# jsduino.net
KiCad netlist of a schematic drawn in Altium Designer
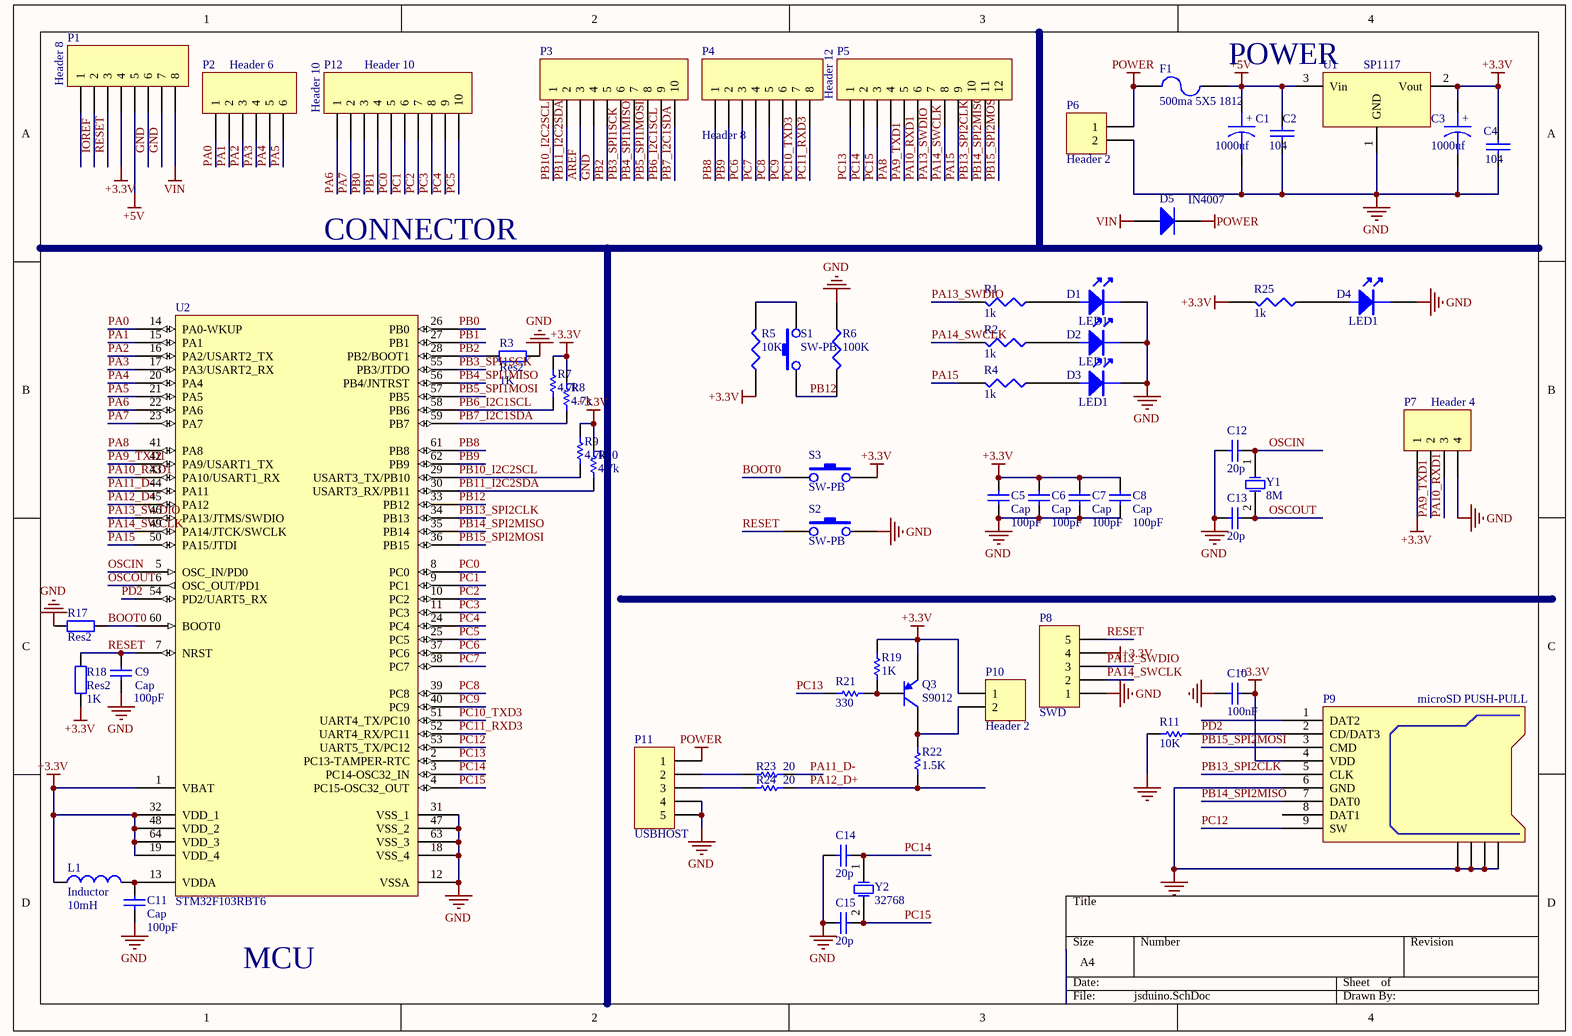
[diagram p0: jsduino.SchDoc]

(export (version "E")
  (design (tool "Eeschema 10.0.6"))
  (components
    (comp (ref "C1")
      (value "1000uf")
      (footprint "c6.3*5.3")
      (description "Capacitor")
      (libsource (lib "*") (part "CAPACITOR POL"))
    )
    (comp (ref "C2")
      (value "104")
      (footprint "0603CC")
      (description "Capacitor")
      (libsource (lib "*") (part "CAP"))
    )
    (comp (ref "C3")
      (value "104")
      (footprint "0603CC")
      (description "Capacitor")
      (libsource (lib "*") (part "CAP"))
    )
    (comp (ref "C4")
      (value "1000uf")
      (footprint "c6.3*5.3")
      (description "Capacitor")
      (libsource (lib "*") (part "CAPACITOR POL"))
    )
    (comp (ref "C5")
      (value "Cap")
      (footprint "0603CC")
      (description "Capacitor")
      (fields (field (name "ALTIUM_VALUE") "100pF") (field (name "PUBLISHER") "Altium Limited"))
      (libsource (lib "Miscellaneous Devices") (part "Cap"))
    )
    (comp (ref "C6")
      (value "Cap")
      (footprint "0603CC")
      (description "Capacitor")
      (fields (field (name "ALTIUM_VALUE") "100pF") (field (name "PUBLISHER") "Altium Limited"))
      (libsource (lib "Miscellaneous Devices") (part "Cap"))
    )
    (comp (ref "C7")
      (value "Cap")
      (footprint "0603CC")
      (description "Capacitor")
      (fields (field (name "ALTIUM_VALUE") "100pF") (field (name "PUBLISHER") "Altium Limited"))
      (libsource (lib "Miscellaneous Devices") (part "Cap"))
    )
    (comp (ref "C8")
      (value "Cap")
      (footprint "0603CC")
      (description "Capacitor")
      (fields (field (name "ALTIUM_VALUE") "100pF") (field (name "PUBLISHER") "Altium Limited"))
      (libsource (lib "Miscellaneous Devices") (part "Cap"))
    )
    (comp (ref "C9")
      (value "Cap")
      (footprint "0603CC")
      (description "Capacitor")
      (fields (field (name "ALTIUM_VALUE") "100pF") (field (name "PUBLISHER") "Altium Limited"))
      (libsource (lib "Miscellaneous Devices") (part "Cap"))
    )
    (comp (ref "C10") (value "100nF") (footprint "0603CC") (libsource (lib "") (part "CAP_1")))
    (comp (ref "C11")
      (value "Cap")
      (footprint "0603CC")
      (description "Capacitor")
      (fields (field (name "ALTIUM_VALUE") "100pF") (field (name "PUBLISHER") "Altium Limited"))
      (libsource (lib "Miscellaneous Devices") (part "Cap"))
    )
    (comp (ref "C12")
      (value "20p")
      (footprint "0603CC")
      (description "Capacitor")
      (fields (field (name "Comment") "Cap") (field (name "PUBLISHER") "Altium Limited"))
      (libsource (lib "Miscellaneous Devices") (part "Cap"))
    )
    (comp (ref "C13")
      (value "20p")
      (footprint "0603CC")
      (description "Capacitor")
      (fields (field (name "Comment") "Cap") (field (name "PUBLISHER") "Altium Limited"))
      (libsource (lib "Miscellaneous Devices") (part "Cap"))
    )
    (comp (ref "C14")
      (value "20p")
      (footprint "0603CC")
      (description "Capacitor")
      (fields (field (name "Comment") "Cap") (field (name "PUBLISHER") "Altium Limited"))
      (libsource (lib "Miscellaneous Devices") (part "Cap"))
    )
    (comp (ref "C15")
      (value "20p")
      (footprint "0603CC")
      (description "Capacitor")
      (fields (field (name "Comment") "Cap") (field (name "PUBLISHER") "Altium Limited"))
      (libsource (lib "Miscellaneous Devices") (part "Cap"))
    )
    (comp (ref "D1") (value "LED1") (footprint "0805LED") (libsource (lib "*") (part "LED")))
    (comp (ref "D2") (value "LED1") (footprint "0805LED") (libsource (lib "*") (part "LED")))
    (comp (ref "D3") (value "LED1") (footprint "0805LED") (libsource (lib "*") (part "LED")))
    (comp (ref "D4") (value "LED1") (footprint "0805LED") (libsource (lib "*") (part "LED")))
    (comp (ref "D5")
      (value "IN4007")
      (footprint "DIODE_SS14")
      (description "Default Diode")
      (fields (field (name "PUBLISHER") "Altium Limited"))
      (libsource (lib "Miscellaneous Devices") (part "Diode"))
    )
    (comp (ref "F1")
      (value "500ma 5X5 1812")
      (footprint "1812R")
      (description "Fuse")
      (fields (field (name "PUBLISHER") "Altium Limited"))
      (libsource (lib "Miscellaneous Devices") (part "Fuse 2"))
    )
    (comp (ref "L1")
      (value "Inductor")
      (footprint "0603RR")
      (fields (field (name "ALTIUM_VALUE") "10mH") (field (name "PUBLISHER") "Altium Limited"))
      (libsource (lib "Miscellaneous Devices") (part "Inductor"))
    )
    (comp (ref "P1")
      (value "Header 8")
      (footprint "HDR1X8")
      (description "Header, 8-Pin")
      (fields (field (name "PUBLISHER") "Altium Limited"))
      (libsource (lib "Miscellaneous Connectors") (part "Header 8"))
    )
    (comp (ref "P2")
      (value "Header 6")
      (footprint "HDR1X6")
      (description "Header, 6-Pin")
      (fields (field (name "PUBLISHER") "Altium Limited"))
      (libsource (lib "Miscellaneous Connectors") (part "Header 6"))
    )
    (comp (ref "P3")
      (value "Header 10")
      (footprint "HDR1X10")
      (description "Header, 10-Pin")
      (fields (field (name "PUBLISHER") "Altium Limited"))
      (libsource (lib "Miscellaneous Connectors") (part "Header 10"))
    )
    (comp (ref "P4")
      (value "Header 8")
      (footprint "HDR1X8")
      (description "Header, 8-Pin")
      (fields (field (name "PUBLISHER") "Altium Limited"))
      (libsource (lib "Miscellaneous Connectors") (part "Header 8"))
    )
    (comp (ref "P5")
      (value "Header 12")
      (footprint "HDR1X12")
      (description "Header, 12-Pin")
      (fields (field (name "PUBLISHER") "Altium Limited"))
      (libsource (lib "Miscellaneous Connectors") (part "Header 12"))
    )
    (comp (ref "P6")
      (value "Header 2")
      (footprint "5VINPUT")
      (description "Header, 2-Pin")
      (fields (field (name "PUBLISHER") "Altium Limited"))
      (libsource (lib "Miscellaneous Connectors") (part "Header 2"))
    )
    (comp (ref "P7")
      (value "Header 4")
      (footprint "HDR1X4")
      (description "Header, 4-Pin")
      (fields (field (name "PUBLISHER") "Altium Limited"))
      (libsource (lib "Miscellaneous Connectors") (part "Header 4"))
    )
    (comp (ref "P8")
      (value "SWD")
      (footprint "HDR1X5")
      (description "Header, 5-Pin")
      (fields (field (name "PUBLISHER") "Altium Limited"))
      (libsource (lib "") (part "Header 5_1"))
    )
    (comp (ref "P9")
      (value "microSD PUSH-PULL")
      (footprint "microSD-1")
      (libsource (lib "s_device") (part "microSD PUSH-PULL"))
    )
    (comp (ref "P10")
      (value "Header 2")
      (footprint "HDR1X2")
      (description "Header, 2-Pin")
      (fields (field (name "PUBLISHER") "Altium Limited"))
      (libsource (lib "") (part "Header 2_1"))
    )
    (comp (ref "P11")
      (value "USBHOST")
      (footprint "USB_mini")
      (description "Header, 5-Pin")
      (fields (field (name "PUBLISHER") "Altium Limited"))
      (libsource (lib "Miscellaneous Connectors") (part "Header 5"))
    )
    (comp (ref "P12")
      (value "Header 10")
      (footprint "HDR1X10")
      (description "Header, 10-Pin")
      (fields (field (name "PUBLISHER") "Altium Limited"))
      (libsource (lib "Miscellaneous Connectors") (part "Header 10"))
    )
    (comp (ref "Q3")
      (value "S9012")
      (footprint "SOT-23")
      (description "PNP General Purpose Amplifier")
      (fields (field (name "PUBLISHER") "Altium Limited"))
      (libsource (lib "hhic") (part "S9012"))
    )
    (comp (ref "R1") (value "1k") (footprint "0603RR") (libsource (lib "*") (part "RES1")))
    (comp (ref "R2") (value "1k") (footprint "0603RR") (libsource (lib "*") (part "RES1")))
    (comp (ref "R3")
      (value "Res2")
      (footprint "0603RR")
      (description "Resistor")
      (fields (field (name "ALTIUM_VALUE") "1K") (field (name "PUBLISHER") "Altium Limited"))
      (libsource (lib "Miscellaneous Devices") (part "Res2"))
    )
    (comp (ref "R4") (value "1k") (footprint "0603RR") (libsource (lib "*") (part "RES1")))
    (comp (ref "R5") (value "10K") (footprint "0603RR") (libsource (lib "*") (part "RES1")))
    (comp (ref "R6") (value "100K") (footprint "0603RR") (libsource (lib "*") (part "RES1")))
    (comp (ref "R7")
      (value "4.7k")
      (footprint "0603RR")
      (description "Semiconductor Resistor")
      (fields (field (name "Comment") "Res Semi") (field (name "PUBLISHER") "Altium Limited"))
      (libsource (lib "Miscellaneous Devices") (part "Res Semi"))
    )
    (comp (ref "R8")
      (value "4.7k")
      (footprint "0603RR")
      (description "Semiconductor Resistor")
      (fields (field (name "Comment") "Res Semi") (field (name "PUBLISHER") "Altium Limited"))
      (libsource (lib "Miscellaneous Devices") (part "Res Semi"))
    )
    (comp (ref "R9")
      (value "4.7k")
      (footprint "0603RR")
      (description "Semiconductor Resistor")
      (fields (field (name "Comment") "Res Semi") (field (name "PUBLISHER") "Altium Limited"))
      (libsource (lib "Miscellaneous Devices") (part "Res Semi"))
    )
    (comp (ref "R10")
      (value "4.7k")
      (footprint "0603RR")
      (description "Semiconductor Resistor")
      (fields (field (name "Comment") "Res Semi") (field (name "PUBLISHER") "Altium Limited"))
      (libsource (lib "Miscellaneous Devices") (part "Res Semi"))
    )
    (comp (ref "R11")
      (value "10K")
      (footprint "0603RR")
      (description "Semiconductor Resistor")
      (fields (field (name "Comment") "Res Semi") (field (name "PUBLISHER") "Altium Limited"))
      (libsource (lib "Miscellaneous Devices") (part "Res Semi"))
    )
    (comp (ref "R17")
      (value "Res2")
      (footprint "0603RR")
      (description "Resistor")
      (fields (field (name "PUBLISHER") "Altium Limited"))
      (libsource (lib "Miscellaneous Devices") (part "Res2"))
    )
    (comp (ref "R18")
      (value "Res2")
      (footprint "0603RR")
      (description "Resistor")
      (fields (field (name "ALTIUM_VALUE") "1K") (field (name "PUBLISHER") "Altium Limited"))
      (libsource (lib "") (part "Res2_1"))
    )
    (comp (ref "R19")
      (value "1K")
      (footprint "0603RR")
      (description "Semiconductor Resistor")
      (fields (field (name "Comment") "Res Semi") (field (name "PUBLISHER") "Altium Limited"))
      (libsource (lib "Miscellaneous Devices") (part "Res Semi"))
    )
    (comp (ref "R21")
      (value "330")
      (footprint "0603RR")
      (description "Semiconductor Resistor")
      (fields (field (name "Comment") "Res Semi") (field (name "PUBLISHER") "Altium Limited"))
      (libsource (lib "Miscellaneous Devices") (part "Res Semi"))
    )
    (comp (ref "R22")
      (value "1.5K")
      (footprint "0603RR")
      (description "Semiconductor Resistor")
      (fields (field (name "Comment") "Res Semi") (field (name "PUBLISHER") "Altium Limited"))
      (libsource (lib "Miscellaneous Devices") (part "Res Semi"))
    )
    (comp (ref "R23")
      (value "20")
      (footprint "0603RR")
      (description "Semiconductor Resistor")
      (fields (field (name "Comment") "Res Semi") (field (name "PUBLISHER") "Altium Limited"))
      (libsource (lib "Miscellaneous Devices") (part "Res Semi"))
    )
    (comp (ref "R24")
      (value "20")
      (footprint "0603RR")
      (description "Semiconductor Resistor")
      (fields (field (name "Comment") "Res Semi") (field (name "PUBLISHER") "Altium Limited"))
      (libsource (lib "Miscellaneous Devices") (part "Res Semi"))
    )
    (comp (ref "R25") (value "1k") (footprint "0603RR") (libsource (lib "*") (part "RES1")))
    (comp (ref "S1") (value "SW-PB") (footprint "KEY_5*5*X") (libsource (lib "*") (part "SW-PB")))
    (comp (ref "S2") (value "SW-PB") (footprint "KEY_5*5*X") (libsource (lib "*") (part "SW-PB")))
    (comp (ref "S3") (value "SW-PB") (footprint "KEY_5*5*X") (libsource (lib "*") (part "SW-PB")))
    (comp (ref "U1") (value "SP1117") (footprint "SOT-223") (libsource (lib "hhregulator") (part "SP1117")))
    (comp (ref "U2")
      (value "STM32F103RBT6")
      (footprint "LQFP64_M")
      (description "STM32 ARM-based 32-bit MCU with 128 Kbytes Flash, 64-pin LQFP, Industrial Temperature")
      (fields (field (name "PUBLISHER") "*"))
      (libsource (lib "hhmcu") (part "STM32F103RBT6"))
    )
    (comp (ref "Y1")
      (value "8M")
      (footprint "XTAL_smd1")
      (description "Crystal Oscillator")
      (fields (field (name "PUBLISHER") "Altium Limited"))
      (libsource (lib "Miscellaneous Devices") (part "XTAL"))
    )
    (comp (ref "Y2")
      (value "32768")
      (footprint "XTAL_32768_HH")
      (description "Crystal Oscillator")
      (fields (field (name "PUBLISHER") "Altium Limited"))
      (libsource (lib "Miscellaneous Devices") (part "XTAL"))
    )
  )
  (nets
    (net (code "1") (name "+3.3V") (class "Default")
      (node (ref "C10") (pin "2") (pinfunction "2_2") (pintype "passive"))
      (node (ref "C3") (pin "1") (pinfunction "1_1") (pintype "passive"))
      (node (ref "C4") (pin "1") (pinfunction "1_1") (pintype "passive"))
      (node (ref "C5") (pin "2") (pinfunction "2_2") (pintype "passive"))
      (node (ref "C6") (pin "2") (pinfunction "2_2") (pintype "passive"))
      (node (ref "C7") (pin "2") (pinfunction "2_2") (pintype "passive"))
      (node (ref "C8") (pin "2") (pinfunction "2_2") (pintype "passive"))
      (node (ref "L1") (pin "1") (pinfunction "1_1") (pintype "passive"))
      (node (ref "P1") (pin "4") (pinfunction "4_4") (pintype "passive"))
      (node (ref "P10") (pin "1") (pinfunction "1_1") (pintype "passive"))
      (node (ref "P7") (pin "1") (pinfunction "1_1") (pintype "passive"))
      (node (ref "P8") (pin "4") (pinfunction "4_4") (pintype "passive"))
      (node (ref "P9") (pin "4") (pinfunction "VDD_4") (pintype "passive"))
      (node (ref "Q3") (pin "2") (pinfunction "E_2") (pintype "passive"))
      (node (ref "R10") (pin "1") (pinfunction "1_1") (pintype "passive"))
      (node (ref "R18") (pin "1") (pinfunction "1_1") (pintype "passive"))
      (node (ref "R19") (pin "2") (pinfunction "2_2") (pintype "passive"))
      (node (ref "R25") (pin "2") (pinfunction "2_2") (pintype "passive"))
      (node (ref "R5") (pin "1") (pinfunction "1_1") (pintype "passive"))
      (node (ref "R7") (pin "1") (pinfunction "1_1") (pintype "passive"))
      (node (ref "R8") (pin "1") (pinfunction "1_1") (pintype "passive"))
      (node (ref "R9") (pin "1") (pinfunction "1_1") (pintype "passive"))
      (node (ref "S3") (pin "2") (pinfunction "2_2") (pintype "passive"))
      (node (ref "U1") (pin "2") (pinfunction "Vout_2") (pintype "passive"))
      (node (ref "U2") (pin "1") (pinfunction "VBAT_1") (pintype "power_in"))
      (node (ref "U2") (pin "19") (pinfunction "VDD_4_19") (pintype "power_in"))
      (node (ref "U2") (pin "32") (pinfunction "VDD_1_32") (pintype "power_in"))
      (node (ref "U2") (pin "48") (pinfunction "VDD_2_48") (pintype "power_in"))
      (node (ref "U2") (pin "64") (pinfunction "VDD_3_64") (pintype "power_in"))
    )
    (net (code "2") (name "+5V") (class "Default")
      (node (ref "C1") (pin "1") (pinfunction "1_1") (pintype "passive"))
      (node (ref "C2") (pin "1") (pinfunction "1_1") (pintype "passive"))
      (node (ref "F1") (pin "2") (pinfunction "2_2") (pintype "passive"))
      (node (ref "P1") (pin "5") (pinfunction "5_5") (pintype "passive"))
      (node (ref "U1") (pin "3") (pinfunction "Vin_3") (pintype "passive"))
    )
    (net (code "3") (name "/AREF") (class "Default")
      (node (ref "P3") (pin "3") (pinfunction "3_3") (pintype "passive"))
    )
    (net (code "4") (name "/BOOT0") (class "Default")
      (node (ref "R17") (pin "1") (pinfunction "1_1") (pintype "passive"))
      (node (ref "S3") (pin "1") (pinfunction "1_1") (pintype "passive"))
      (node (ref "U2") (pin "60") (pinfunction "BOOT0_60") (pintype "input"))
    )
    (net (code "5") (name "/IOREF") (class "Default")
      (node (ref "P1") (pin "2") (pinfunction "2_2") (pintype "passive"))
    )
    (net (code "6") (name "/OSCIN") (class "Default")
      (node (ref "C12") (pin "1") (pinfunction "1_1") (pintype "passive"))
      (node (ref "U2") (pin "5") (pinfunction "OSC_IN/PD0_5") (pintype "input"))
      (node (ref "Y1") (pin "1") (pinfunction "OSC1_1") (pintype "passive"))
    )
    (net (code "7") (name "/OSCOUT") (class "Default")
      (node (ref "C13") (pin "1") (pinfunction "1_1") (pintype "passive"))
      (node (ref "U2") (pin "6") (pinfunction "OSC_OUT/PD1_6") (pintype "output"))
      (node (ref "Y1") (pin "2") (pinfunction "OSC2_2") (pintype "passive"))
    )
    (net (code "8") (name "/PA0") (class "Default")
      (node (ref "P2") (pin "1") (pinfunction "1_1") (pintype "passive"))
      (node (ref "U2") (pin "14") (pinfunction "PA0-WKUP_14") (pintype "bidirectional"))
    )
    (net (code "9") (name "/PA1") (class "Default")
      (node (ref "P2") (pin "2") (pinfunction "2_2") (pintype "passive"))
      (node (ref "U2") (pin "15") (pinfunction "PA1_15") (pintype "bidirectional"))
    )
    (net (code "10") (name "/PA2") (class "Default")
      (node (ref "P2") (pin "3") (pinfunction "3_3") (pintype "passive"))
      (node (ref "U2") (pin "16") (pinfunction "PA2/USART2_TX_16") (pintype "bidirectional"))
    )
    (net (code "11") (name "/PA3") (class "Default")
      (node (ref "P2") (pin "4") (pinfunction "4_4") (pintype "passive"))
      (node (ref "U2") (pin "17") (pinfunction "PA3/USART2_RX_17") (pintype "bidirectional"))
    )
    (net (code "12") (name "/PA4") (class "Default")
      (node (ref "P2") (pin "5") (pinfunction "5_5") (pintype "passive"))
      (node (ref "U2") (pin "20") (pinfunction "PA4_20") (pintype "bidirectional"))
    )
    (net (code "13") (name "/PA5") (class "Default")
      (node (ref "P2") (pin "6") (pinfunction "6_6") (pintype "passive"))
      (node (ref "U2") (pin "21") (pinfunction "PA5_21") (pintype "bidirectional"))
    )
    (net (code "14") (name "/PA6") (class "Default")
      (node (ref "P12") (pin "1") (pinfunction "1_1") (pintype "passive"))
      (node (ref "U2") (pin "22") (pinfunction "PA6_22") (pintype "bidirectional"))
    )
    (net (code "15") (name "/PA7") (class "Default")
      (node (ref "P12") (pin "2") (pinfunction "2_2") (pintype "passive"))
      (node (ref "U2") (pin "23") (pinfunction "PA7_23") (pintype "bidirectional"))
    )
    (net (code "16") (name "/PA8") (class "Default")
      (node (ref "P5") (pin "4") (pinfunction "4_4") (pintype "passive"))
      (node (ref "U2") (pin "41") (pinfunction "PA8_41") (pintype "bidirectional"))
    )
    (net (code "17") (name "/PA9_TXD1") (class "Default")
      (node (ref "P5") (pin "5") (pinfunction "5_5") (pintype "passive"))
      (node (ref "P7") (pin "2") (pinfunction "2_2") (pintype "passive"))
      (node (ref "U2") (pin "42") (pinfunction "PA9/USART1_TX_42") (pintype "bidirectional"))
    )
    (net (code "18") (name "/PA10_RXD1") (class "Default")
      (node (ref "P5") (pin "6") (pinfunction "6_6") (pintype "passive"))
      (node (ref "P7") (pin "3") (pinfunction "3_3") (pintype "passive"))
      (node (ref "U2") (pin "43") (pinfunction "PA10/USART1_RX_43") (pintype "bidirectional"))
    )
    (net (code "19") (name "/PA11_D-") (class "Default")
      (node (ref "R23") (pin "2") (pinfunction "2_2") (pintype "passive"))
      (node (ref "U2") (pin "44") (pinfunction "PA11_44") (pintype "bidirectional"))
    )
    (net (code "20") (name "/PA12_D+") (class "Default")
      (node (ref "R22") (pin "2") (pinfunction "2_2") (pintype "passive"))
      (node (ref "R24") (pin "2") (pinfunction "2_2") (pintype "passive"))
      (node (ref "U2") (pin "45") (pinfunction "PA12_45") (pintype "bidirectional"))
    )
    (net (code "21") (name "/PA13_SWDIO") (class "Default")
      (node (ref "P5") (pin "7") (pinfunction "7_7") (pintype "passive"))
      (node (ref "P8") (pin "3") (pinfunction "3_3") (pintype "passive"))
      (node (ref "R1") (pin "2") (pinfunction "2_2") (pintype "passive"))
      (node (ref "U2") (pin "46") (pinfunction "PA13/JTMS/SWDIO_46") (pintype "bidirectional"))
    )
    (net (code "22") (name "/PA14_SWCLK") (class "Default")
      (node (ref "P5") (pin "8") (pinfunction "8_8") (pintype "passive"))
      (node (ref "P8") (pin "2") (pinfunction "2_2") (pintype "passive"))
      (node (ref "R2") (pin "2") (pinfunction "2_2") (pintype "passive"))
      (node (ref "U2") (pin "49") (pinfunction "PA14/JTCK/SWCLK_49") (pintype "bidirectional"))
    )
    (net (code "23") (name "/PA15") (class "Default")
      (node (ref "P5") (pin "9") (pinfunction "9_9") (pintype "passive"))
      (node (ref "R4") (pin "2") (pinfunction "2_2") (pintype "passive"))
      (node (ref "U2") (pin "50") (pinfunction "PA15/JTDI_50") (pintype "bidirectional"))
    )
    (net (code "24") (name "/PB0") (class "Default")
      (node (ref "P12") (pin "3") (pinfunction "3_3") (pintype "passive"))
      (node (ref "U2") (pin "26") (pinfunction "PB0_26") (pintype "bidirectional"))
    )
    (net (code "25") (name "/PB1") (class "Default")
      (node (ref "P12") (pin "4") (pinfunction "4_4") (pintype "passive"))
      (node (ref "U2") (pin "27") (pinfunction "PB1_27") (pintype "bidirectional"))
    )
    (net (code "26") (name "/PB2") (class "Default")
      (node (ref "P3") (pin "5") (pinfunction "5_5") (pintype "passive"))
      (node (ref "R3") (pin "2") (pinfunction "2_2") (pintype "passive"))
      (node (ref "U2") (pin "28") (pinfunction "PB2/BOOT1_28") (pintype "bidirectional"))
    )
    (net (code "27") (name "/PB3_SPI1SCK") (class "Default")
      (node (ref "P3") (pin "6") (pinfunction "6_6") (pintype "passive"))
      (node (ref "U2") (pin "55") (pinfunction "PB3/JTDO_55") (pintype "bidirectional"))
    )
    (net (code "28") (name "/PB4_SPI1MISO") (class "Default")
      (node (ref "P3") (pin "7") (pinfunction "7_7") (pintype "passive"))
      (node (ref "U2") (pin "56") (pinfunction "PB4/JNTRST_56") (pintype "bidirectional"))
    )
    (net (code "29") (name "/PB5_SPI1MOSI") (class "Default")
      (node (ref "P3") (pin "8") (pinfunction "8_8") (pintype "passive"))
      (node (ref "U2") (pin "57") (pinfunction "PB5_57") (pintype "bidirectional"))
    )
    (net (code "30") (name "/PB6_I2C1SCL") (class "Default")
      (node (ref "P3") (pin "9") (pinfunction "9_9") (pintype "passive"))
      (node (ref "R7") (pin "2") (pinfunction "2_2") (pintype "passive"))
      (node (ref "U2") (pin "58") (pinfunction "PB6_58") (pintype "bidirectional"))
    )
    (net (code "31") (name "/PB7_I2C1SDA") (class "Default")
      (node (ref "P3") (pin "10") (pinfunction "10_10") (pintype "passive"))
      (node (ref "R8") (pin "2") (pinfunction "2_2") (pintype "passive"))
      (node (ref "U2") (pin "59") (pinfunction "PB7_59") (pintype "bidirectional"))
    )
    (net (code "32") (name "/PB8") (class "Default")
      (node (ref "P4") (pin "1") (pinfunction "1_1") (pintype "passive"))
      (node (ref "U2") (pin "61") (pinfunction "PB8_61") (pintype "bidirectional"))
    )
    (net (code "33") (name "/PB9") (class "Default")
      (node (ref "P4") (pin "2") (pinfunction "2_2") (pintype "passive"))
      (node (ref "U2") (pin "62") (pinfunction "PB9_62") (pintype "bidirectional"))
    )
    (net (code "34") (name "/PB10_I2C2SCL") (class "Default")
      (node (ref "P3") (pin "1") (pinfunction "1_1") (pintype "passive"))
      (node (ref "R9") (pin "2") (pinfunction "2_2") (pintype "passive"))
      (node (ref "U2") (pin "29") (pinfunction "USART3_TX/PB10_29") (pintype "bidirectional"))
    )
    (net (code "35") (name "/PB11_I2C2SDA") (class "Default")
      (node (ref "P3") (pin "2") (pinfunction "2_2") (pintype "passive"))
      (node (ref "R10") (pin "2") (pinfunction "2_2") (pintype "passive"))
      (node (ref "U2") (pin "30") (pinfunction "USART3_RX/PB11_30") (pintype "bidirectional"))
    )
    (net (code "36") (name "/PB12") (class "Default")
      (node (ref "R6") (pin "2") (pinfunction "2_2") (pintype "passive"))
      (node (ref "S1") (pin "1") (pinfunction "1_1") (pintype "passive"))
      (node (ref "U2") (pin "33") (pinfunction "PB12_33") (pintype "bidirectional"))
    )
    (net (code "37") (name "/PB13_SPI2CLK") (class "Default")
      (node (ref "P5") (pin "10") (pinfunction "10_10") (pintype "passive"))
      (node (ref "P9") (pin "5") (pinfunction "CLK_5") (pintype "passive"))
      (node (ref "U2") (pin "34") (pinfunction "PB13_34") (pintype "bidirectional"))
    )
    (net (code "38") (name "/PB14_SPI2MISO") (class "Default")
      (node (ref "P5") (pin "11") (pinfunction "11_11") (pintype "passive"))
      (node (ref "P9") (pin "7") (pinfunction "DAT0_7") (pintype "passive"))
      (node (ref "U2") (pin "35") (pinfunction "PB14_35") (pintype "bidirectional"))
    )
    (net (code "39") (name "/PB15_SPI2MOSI") (class "Default")
      (node (ref "P5") (pin "12") (pinfunction "12_12") (pintype "passive"))
      (node (ref "P9") (pin "3") (pinfunction "CMD_3") (pintype "passive"))
      (node (ref "U2") (pin "36") (pinfunction "PB15_36") (pintype "bidirectional"))
    )
    (net (code "40") (name "/PC0") (class "Default")
      (node (ref "P12") (pin "5") (pinfunction "5_5") (pintype "passive"))
      (node (ref "U2") (pin "8") (pinfunction "PC0_8") (pintype "bidirectional"))
    )
    (net (code "41") (name "/PC1") (class "Default")
      (node (ref "P12") (pin "6") (pinfunction "6_6") (pintype "passive"))
      (node (ref "U2") (pin "9") (pinfunction "PC1_9") (pintype "bidirectional"))
    )
    (net (code "42") (name "/PC2") (class "Default")
      (node (ref "P12") (pin "7") (pinfunction "7_7") (pintype "passive"))
      (node (ref "U2") (pin "10") (pinfunction "PC2_10") (pintype "bidirectional"))
    )
    (net (code "43") (name "/PC3") (class "Default")
      (node (ref "P12") (pin "8") (pinfunction "8_8") (pintype "passive"))
      (node (ref "U2") (pin "11") (pinfunction "PC3_11") (pintype "bidirectional"))
    )
    (net (code "44") (name "/PC4") (class "Default")
      (node (ref "P12") (pin "9") (pinfunction "9_9") (pintype "passive"))
      (node (ref "U2") (pin "24") (pinfunction "PC4_24") (pintype "bidirectional"))
    )
    (net (code "45") (name "/PC5") (class "Default")
      (node (ref "P12") (pin "10") (pinfunction "10_10") (pintype "passive"))
      (node (ref "U2") (pin "25") (pinfunction "PC5_25") (pintype "bidirectional"))
    )
    (net (code "46") (name "/PC6") (class "Default")
      (node (ref "P4") (pin "3") (pinfunction "3_3") (pintype "passive"))
      (node (ref "U2") (pin "37") (pinfunction "PC6_37") (pintype "bidirectional"))
    )
    (net (code "47") (name "/PC7") (class "Default")
      (node (ref "P4") (pin "4") (pinfunction "4_4") (pintype "passive"))
      (node (ref "U2") (pin "38") (pinfunction "PC7_38") (pintype "bidirectional"))
    )
    (net (code "48") (name "/PC8") (class "Default")
      (node (ref "P4") (pin "5") (pinfunction "5_5") (pintype "passive"))
      (node (ref "U2") (pin "39") (pinfunction "PC8_39") (pintype "bidirectional"))
    )
    (net (code "49") (name "/PC9") (class "Default")
      (node (ref "P4") (pin "6") (pinfunction "6_6") (pintype "passive"))
      (node (ref "U2") (pin "40") (pinfunction "PC9_40") (pintype "bidirectional"))
    )
    (net (code "50") (name "/PC10_TXD3") (class "Default")
      (node (ref "P4") (pin "7") (pinfunction "7_7") (pintype "passive"))
      (node (ref "U2") (pin "51") (pinfunction "UART4_TX/PC10_51") (pintype "bidirectional"))
    )
    (net (code "51") (name "/PC11_RXD3") (class "Default")
      (node (ref "P4") (pin "8") (pinfunction "8_8") (pintype "passive"))
      (node (ref "U2") (pin "52") (pinfunction "UART4_RX/PC11_52") (pintype "bidirectional"))
    )
    (net (code "52") (name "/PC12") (class "Default")
      (node (ref "P9") (pin "9") (pinfunction "SW_9") (pintype "passive"))
      (node (ref "U2") (pin "53") (pinfunction "UART5_TX/PC12_53") (pintype "bidirectional"))
    )
    (net (code "53") (name "/PC13") (class "Default")
      (node (ref "P5") (pin "1") (pinfunction "1_1") (pintype "passive"))
      (node (ref "R21") (pin "1") (pinfunction "1_1") (pintype "passive"))
      (node (ref "U2") (pin "2") (pinfunction "PC13-TAMPER-RTC_2") (pintype "bidirectional"))
    )
    (net (code "54") (name "/PC14") (class "Default")
      (node (ref "C14") (pin "1") (pinfunction "1_1") (pintype "passive"))
      (node (ref "P5") (pin "2") (pinfunction "2_2") (pintype "passive"))
      (node (ref "U2") (pin "3") (pinfunction "PC14-OSC32_IN_3") (pintype "bidirectional"))
      (node (ref "Y2") (pin "1") (pinfunction "OSC1_1") (pintype "passive"))
    )
    (net (code "55") (name "/PC15") (class "Default")
      (node (ref "C15") (pin "1") (pinfunction "1_1") (pintype "passive"))
      (node (ref "P5") (pin "3") (pinfunction "3_3") (pintype "passive"))
      (node (ref "U2") (pin "4") (pinfunction "PC15-OSC32_OUT_4") (pintype "bidirectional"))
      (node (ref "Y2") (pin "2") (pinfunction "OSC2_2") (pintype "passive"))
    )
    (net (code "56") (name "/PD2") (class "Default")
      (node (ref "P9") (pin "2") (pinfunction "CD/DAT3_2") (pintype "passive"))
      (node (ref "R11") (pin "1") (pinfunction "1_1") (pintype "passive"))
      (node (ref "U2") (pin "54") (pinfunction "PD2/UART5_RX_54") (pintype "bidirectional"))
    )
    (net (code "57") (name "/RESET") (class "Default")
      (node (ref "C9") (pin "2") (pinfunction "2_2") (pintype "passive"))
      (node (ref "P1") (pin "3") (pinfunction "3_3") (pintype "passive"))
      (node (ref "P8") (pin "5") (pinfunction "5_5") (pintype "passive"))
      (node (ref "R18") (pin "2") (pinfunction "2_2") (pintype "passive"))
      (node (ref "S2") (pin "1") (pinfunction "1_1") (pintype "passive"))
      (node (ref "U2") (pin "7") (pinfunction "NRST_7") (pintype "bidirectional"))
    )
    (net (code "58") (name "GND") (class "Default")
      (node (ref "C1") (pin "2") (pinfunction "2_2") (pintype "passive"))
      (node (ref "C10") (pin "1") (pinfunction "1_1") (pintype "passive"))
      (node (ref "C11") (pin "1") (pinfunction "1_1") (pintype "passive"))
      (node (ref "C12") (pin "2") (pinfunction "2_2") (pintype "passive"))
      (node (ref "C13") (pin "2") (pinfunction "2_2") (pintype "passive"))
      (node (ref "C14") (pin "2") (pinfunction "2_2") (pintype "passive"))
      (node (ref "C15") (pin "2") (pinfunction "2_2") (pintype "passive"))
      (node (ref "C2") (pin "2") (pinfunction "2_2") (pintype "passive"))
      (node (ref "C3") (pin "2") (pinfunction "2_2") (pintype "passive"))
      (node (ref "C4") (pin "2") (pinfunction "2_2") (pintype "passive"))
      (node (ref "C5") (pin "1") (pinfunction "1_1") (pintype "passive"))
      (node (ref "C6") (pin "1") (pinfunction "1_1") (pintype "passive"))
      (node (ref "C7") (pin "1") (pinfunction "1_1") (pintype "passive"))
      (node (ref "C8") (pin "1") (pinfunction "1_1") (pintype "passive"))
      (node (ref "C9") (pin "1") (pinfunction "1_1") (pintype "passive"))
      (node (ref "D1") (pin "2") (pinfunction "2_2") (pintype "passive"))
      (node (ref "D2") (pin "2") (pinfunction "2_2") (pintype "passive"))
      (node (ref "D3") (pin "2") (pinfunction "2_2") (pintype "passive"))
      (node (ref "D4") (pin "2") (pinfunction "2_2") (pintype "passive"))
      (node (ref "P1") (pin "6") (pinfunction "6_6") (pintype "passive"))
      (node (ref "P1") (pin "7") (pinfunction "7_7") (pintype "passive"))
      (node (ref "P11") (pin "4") (pinfunction "4_4") (pintype "passive"))
      (node (ref "P11") (pin "5") (pinfunction "5_5") (pintype "passive"))
      (node (ref "P3") (pin "4") (pinfunction "4_4") (pintype "passive"))
      (node (ref "P6") (pin "2") (pinfunction "2_2") (pintype "passive"))
      (node (ref "P7") (pin "4") (pinfunction "4_4") (pintype "passive"))
      (node (ref "P8") (pin "1") (pinfunction "1_1") (pintype "passive"))
      (node (ref "P9") (pin "6") (pinfunction "GND_6") (pintype "passive"))
      (node (ref "P9") (pin "GP1") (pintype "passive"))
      (node (ref "P9") (pin "GP2") (pintype "passive"))
      (node (ref "P9") (pin "GP3") (pintype "passive"))
      (node (ref "P9") (pin "GP4") (pintype "passive"))
      (node (ref "R11") (pin "2") (pinfunction "2_2") (pintype "passive"))
      (node (ref "R17") (pin "2") (pinfunction "2_2") (pintype "passive"))
      (node (ref "R3") (pin "1") (pinfunction "1_1") (pintype "passive"))
      (node (ref "R6") (pin "1") (pinfunction "1_1") (pintype "passive"))
      (node (ref "S2") (pin "2") (pinfunction "2_2") (pintype "passive"))
      (node (ref "U1") (pin "1") (pinfunction "GND_1") (pintype "passive"))
      (node (ref "U2") (pin "12") (pinfunction "VSSA_12") (pintype "power_in"))
      (node (ref "U2") (pin "18") (pinfunction "VSS_4_18") (pintype "power_in"))
      (node (ref "U2") (pin "31") (pinfunction "VSS_1_31") (pintype "power_in"))
      (node (ref "U2") (pin "47") (pinfunction "VSS_2_47") (pintype "power_in"))
      (node (ref "U2") (pin "63") (pinfunction "VSS_3_63") (pintype "power_in"))
    )
    (net (code "59") (name "Net-(D1-Pad1)") (class "Default")
      (node (ref "D1") (pin "1") (pinfunction "1_1") (pintype "passive"))
      (node (ref "R1") (pin "1") (pinfunction "1_1") (pintype "passive"))
    )
    (net (code "60") (name "Net-(D2-Pad1)") (class "Default")
      (node (ref "D2") (pin "1") (pinfunction "1_1") (pintype "passive"))
      (node (ref "R2") (pin "1") (pinfunction "1_1") (pintype "passive"))
    )
    (net (code "61") (name "Net-(D3-Pad1)") (class "Default")
      (node (ref "D3") (pin "1") (pinfunction "1_1") (pintype "passive"))
      (node (ref "R4") (pin "1") (pinfunction "1_1") (pintype "passive"))
    )
    (net (code "62") (name "Net-(D4-Pad1)") (class "Default")
      (node (ref "D4") (pin "1") (pinfunction "1_1") (pintype "passive"))
      (node (ref "R25") (pin "1") (pinfunction "1_1") (pintype "passive"))
    )
    (net (code "63") (name "Net-(P11-Pad2)") (class "Default")
      (node (ref "P11") (pin "2") (pinfunction "2_2") (pintype "passive"))
      (node (ref "R23") (pin "1") (pinfunction "1_1") (pintype "passive"))
    )
    (net (code "64") (name "Net-(P11-Pad3)") (class "Default")
      (node (ref "P11") (pin "3") (pinfunction "3_3") (pintype "passive"))
      (node (ref "R24") (pin "1") (pinfunction "1_1") (pintype "passive"))
    )
    (net (code "65") (name "Net-(Q3-B)") (class "Default")
      (node (ref "Q3") (pin "1") (pinfunction "B_1") (pintype "passive"))
      (node (ref "R19") (pin "1") (pinfunction "1_1") (pintype "passive"))
      (node (ref "R21") (pin "2") (pinfunction "2_2") (pintype "passive"))
    )
    (net (code "66") (name "Net-(Q3-C)") (class "Default")
      (node (ref "P10") (pin "2") (pinfunction "2_2") (pintype "passive"))
      (node (ref "Q3") (pin "3") (pinfunction "C_3") (pintype "passive"))
      (node (ref "R22") (pin "1") (pinfunction "1_1") (pintype "passive"))
    )
    (net (code "67") (name "Net-(R5-Pad2)") (class "Default")
      (node (ref "R5") (pin "2") (pinfunction "2_2") (pintype "passive"))
      (node (ref "S1") (pin "2") (pinfunction "2_2") (pintype "passive"))
    )
    (net (code "68") (name "Net-(U2-VDDA)") (class "Default")
      (node (ref "C11") (pin "2") (pinfunction "2_2") (pintype "passive"))
      (node (ref "L1") (pin "2") (pinfunction "2_2") (pintype "passive"))
      (node (ref "U2") (pin "13") (pinfunction "VDDA_13") (pintype "power_in"))
    )
    (net (code "69") (name "POWER") (class "Default")
      (node (ref "D5") (pin "2") (pinfunction "K_2") (pintype "passive"))
      (node (ref "F1") (pin "1") (pinfunction "1_1") (pintype "passive"))
      (node (ref "P11") (pin "1") (pinfunction "1_1") (pintype "passive"))
      (node (ref "P6") (pin "1") (pinfunction "1_1") (pintype "passive"))
    )
    (net (code "70") (name "VIN") (class "Default")
      (node (ref "D5") (pin "1") (pinfunction "A_1") (pintype "passive"))
      (node (ref "P1") (pin "8") (pinfunction "8_8") (pintype "passive"))
    )
    (net (code "71") (name "unconnected-(P1-Pad1)") (class "Default")
      (node (ref "P1") (pin "1") (pinfunction "1_1") (pintype "passive"))
    )
    (net (code "72") (name "unconnected-(P9-DAT1-Pad8)") (class "Default")
      (node (ref "P9") (pin "8") (pinfunction "DAT1_8") (pintype "passive"))
    )
    (net (code "73") (name "unconnected-(P9-DAT2-Pad1)") (class "Default")
      (node (ref "P9") (pin "1") (pinfunction "DAT2_1") (pintype "passive"))
    )
  )
)
